# bal.net
KiCad netlist of a schematic drawn in EAGLE
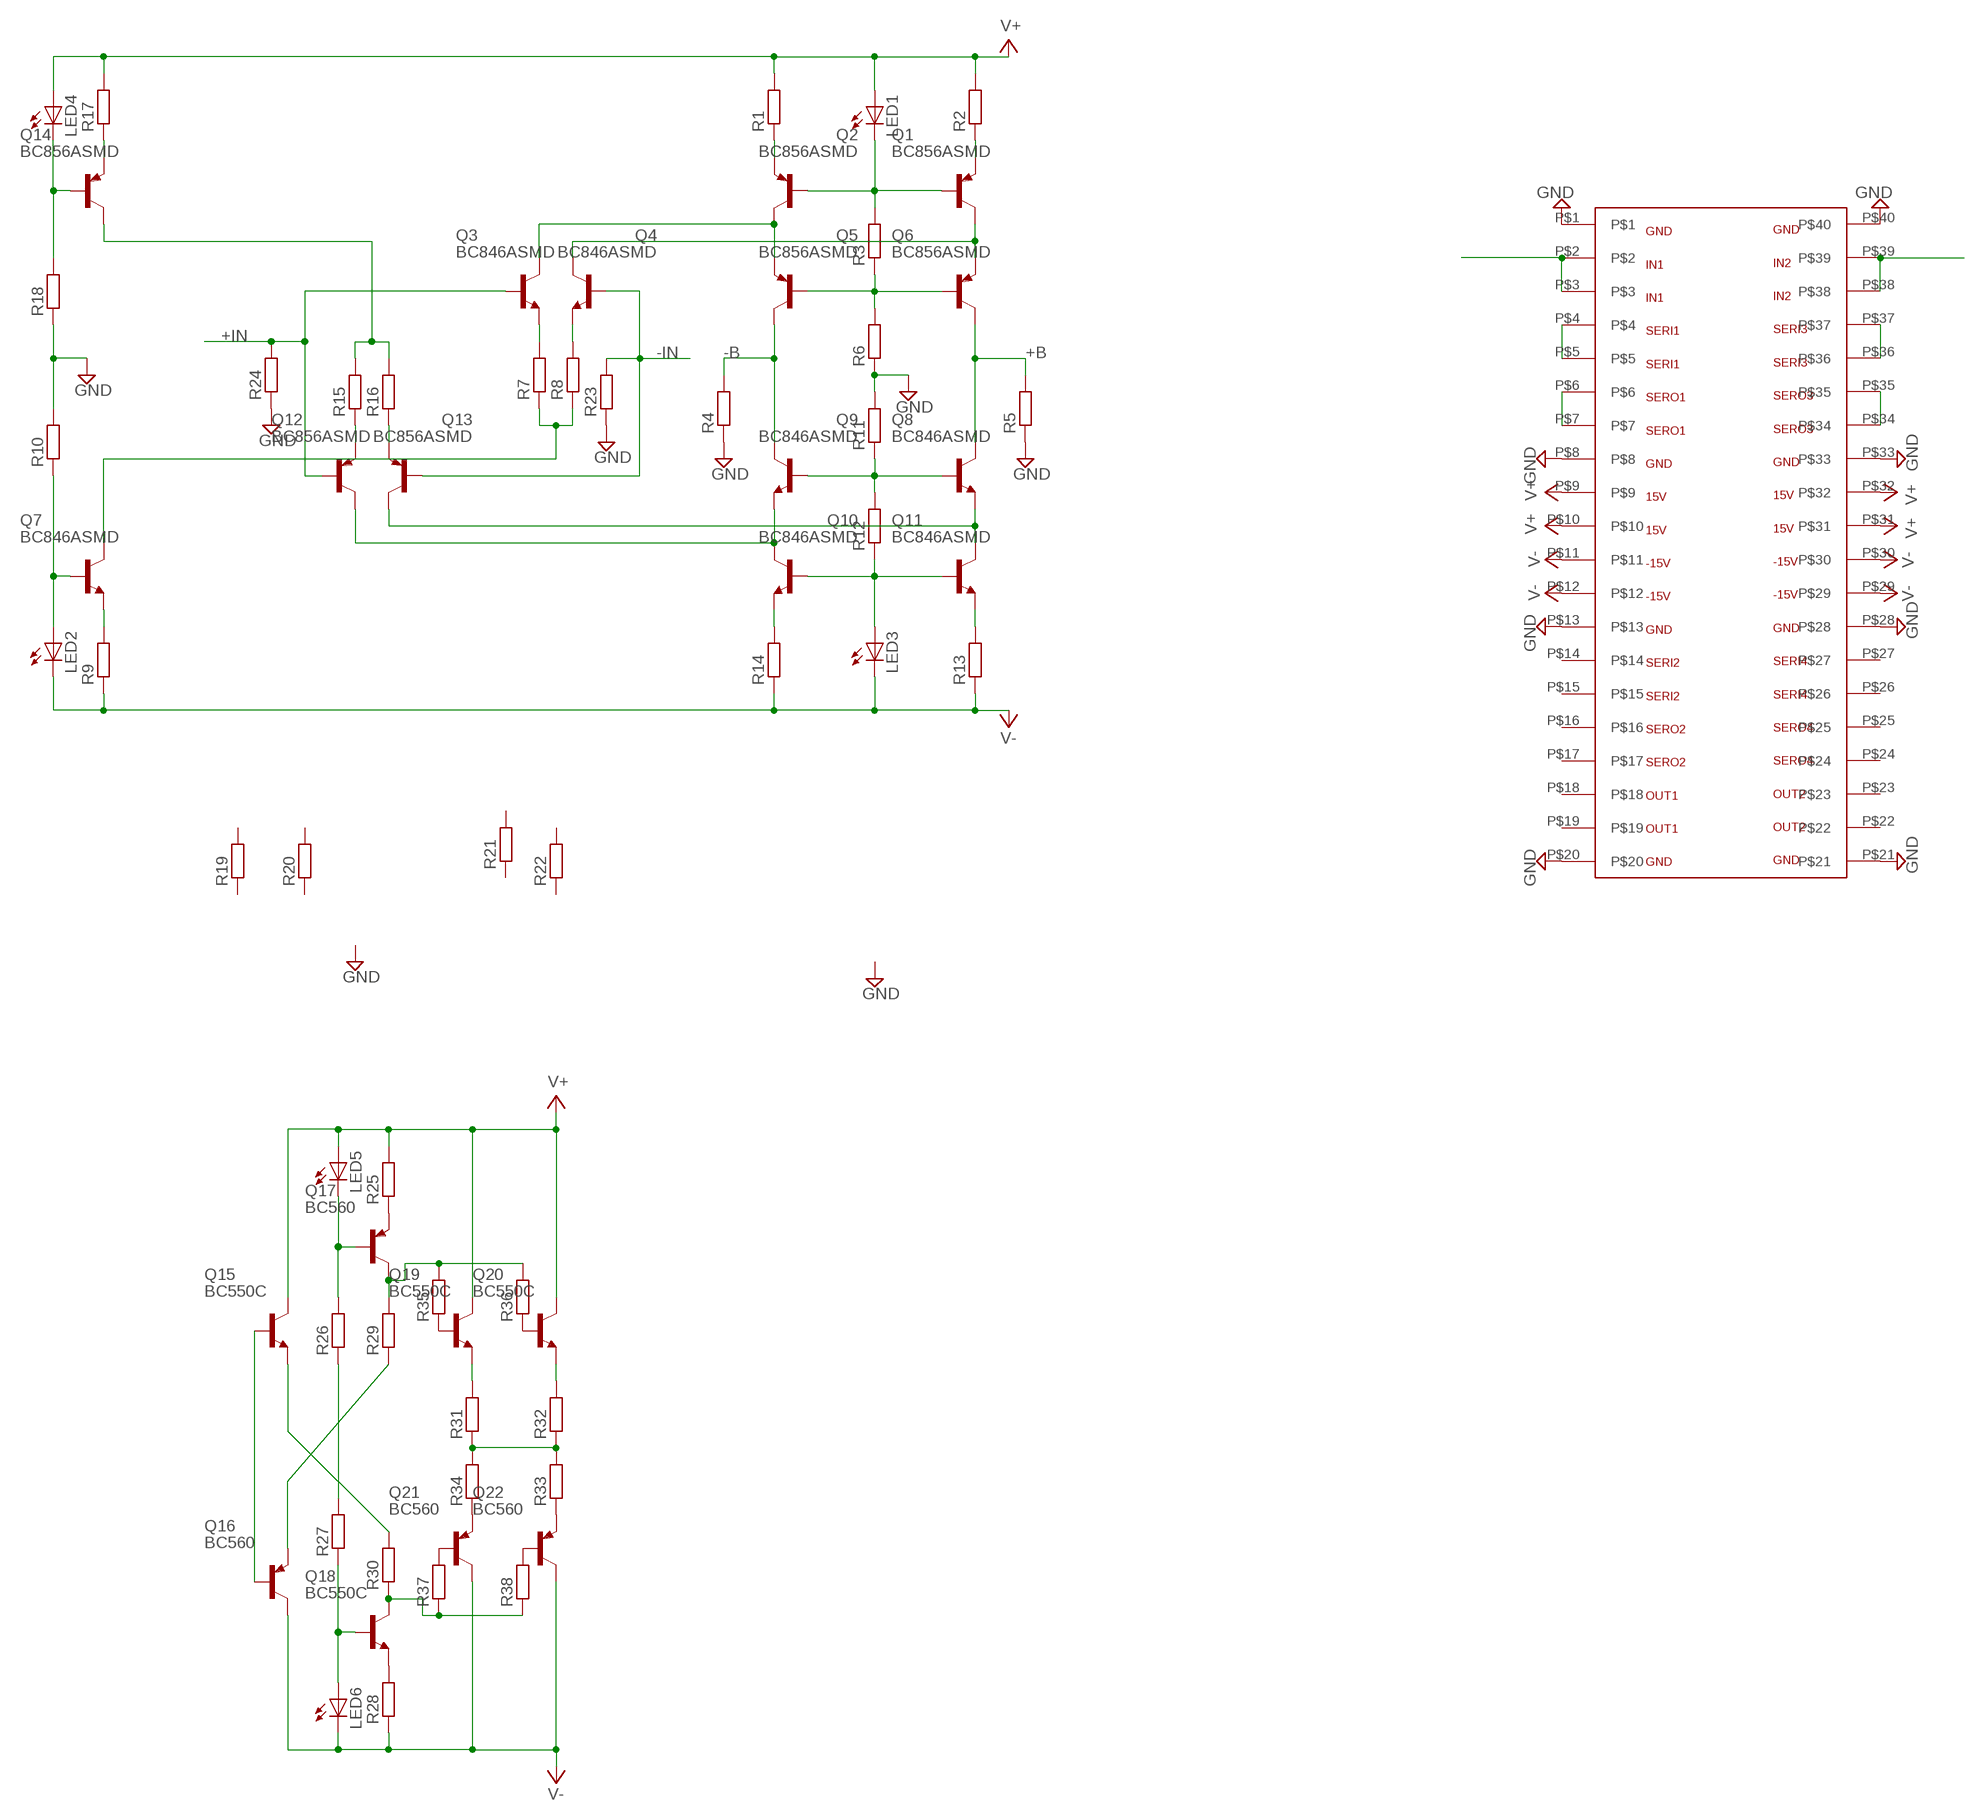
[diagram p0: schematic, sheet 1]

(export (version "E")
  (design (tool "Eeschema 10.0.6"))
  (components
    (comp (ref "LED1")
      (value "LED5MM")
      (footprint "eagle-import:LED5MM")
      (libsource (lib "eagle-import") (part "LED5MM"))
    )
    (comp (ref "LED2")
      (value "LED5MM")
      (footprint "eagle-import:LED5MM")
      (libsource (lib "eagle-import") (part "LED5MM"))
    )
    (comp (ref "LED3")
      (value "LED5MM")
      (footprint "eagle-import:LED5MM")
      (libsource (lib "eagle-import") (part "LED5MM"))
    )
    (comp (ref "LED4")
      (value "LED5MM")
      (footprint "eagle-import:LED5MM")
      (libsource (lib "eagle-import") (part "LED5MM"))
    )
    (comp (ref "LED5")
      (value "LED5MM")
      (footprint "eagle-import:LED5MM")
      (libsource (lib "eagle-import") (part "LED5MM"))
    )
    (comp (ref "LED6")
      (value "LED5MM")
      (footprint "eagle-import:LED5MM")
      (libsource (lib "eagle-import") (part "LED5MM"))
    )
    (comp (ref "Q1")
      (value "BC856ASMD")
      (footprint "eagle-import:SOT23-BEC")
      (libsource (lib "eagle-import") (part "BC856SMDA"))
    )
    (comp (ref "Q2")
      (value "BC856ASMD")
      (footprint "eagle-import:SOT23-BEC")
      (libsource (lib "eagle-import") (part "BC856SMDA"))
    )
    (comp (ref "Q3")
      (value "BC846ASMD")
      (footprint "eagle-import:SOT23")
      (libsource (lib "eagle-import") (part "BC846SMDA"))
    )
    (comp (ref "Q4")
      (value "BC846ASMD")
      (footprint "eagle-import:SOT23")
      (libsource (lib "eagle-import") (part "BC846SMDA"))
    )
    (comp (ref "Q5")
      (value "BC856ASMD")
      (footprint "eagle-import:SOT23-BEC")
      (libsource (lib "eagle-import") (part "BC856SMDA"))
    )
    (comp (ref "Q6")
      (value "BC856ASMD")
      (footprint "eagle-import:SOT23-BEC")
      (libsource (lib "eagle-import") (part "BC856SMDA"))
    )
    (comp (ref "Q7")
      (value "BC846ASMD")
      (footprint "eagle-import:SOT23")
      (libsource (lib "eagle-import") (part "BC846SMDA"))
    )
    (comp (ref "Q8")
      (value "BC846ASMD")
      (footprint "eagle-import:SOT23")
      (libsource (lib "eagle-import") (part "BC846SMDA"))
    )
    (comp (ref "Q9")
      (value "BC846ASMD")
      (footprint "eagle-import:SOT23")
      (libsource (lib "eagle-import") (part "BC846SMDA"))
    )
    (comp (ref "Q10")
      (value "BC846ASMD")
      (footprint "eagle-import:SOT23")
      (libsource (lib "eagle-import") (part "BC846SMDA"))
    )
    (comp (ref "Q11")
      (value "BC846ASMD")
      (footprint "eagle-import:SOT23")
      (libsource (lib "eagle-import") (part "BC846SMDA"))
    )
    (comp (ref "Q12")
      (value "BC856ASMD")
      (footprint "eagle-import:SOT23-BEC")
      (libsource (lib "eagle-import") (part "BC856SMDA"))
    )
    (comp (ref "Q13")
      (value "BC856ASMD")
      (footprint "eagle-import:SOT23-BEC")
      (libsource (lib "eagle-import") (part "BC856SMDA"))
    )
    (comp (ref "Q14")
      (value "BC856ASMD")
      (footprint "eagle-import:SOT23-BEC")
      (libsource (lib "eagle-import") (part "BC856SMDA"))
    )
    (comp (ref "Q15")
      (value "BC550C")
      (footprint "eagle-import:TO92-EBC")
      (libsource (lib "eagle-import") (part "BC550C"))
    )
    (comp (ref "Q16")
      (value "BC560")
      (footprint "eagle-import:TO92_1")
      (libsource (lib "eagle-import") (part "BC560"))
    )
    (comp (ref "Q17")
      (value "BC560")
      (footprint "eagle-import:TO92_1")
      (libsource (lib "eagle-import") (part "BC560"))
    )
    (comp (ref "Q18")
      (value "BC550C")
      (footprint "eagle-import:TO92-EBC")
      (libsource (lib "eagle-import") (part "BC550C"))
    )
    (comp (ref "Q19")
      (value "BC550C")
      (footprint "eagle-import:TO92-EBC")
      (libsource (lib "eagle-import") (part "BC550C"))
    )
    (comp (ref "Q20")
      (value "BC550C")
      (footprint "eagle-import:TO92-EBC")
      (libsource (lib "eagle-import") (part "BC550C"))
    )
    (comp (ref "Q21")
      (value "BC560")
      (footprint "eagle-import:TO92_1")
      (libsource (lib "eagle-import") (part "BC560"))
    )
    (comp (ref "Q22")
      (value "BC560")
      (footprint "eagle-import:TO92_1")
      (libsource (lib "eagle-import") (part "BC560"))
    )
    (comp (ref "R1")
      (value "R-EU_MELF0204W")
      (footprint "eagle-import:MINI_MELF-0204W")
      (libsource (lib "eagle-import") (part "R-EU_MELF0204W"))
    )
    (comp (ref "R2")
      (value "R-EU_MELF0204W")
      (footprint "eagle-import:MINI_MELF-0204W")
      (libsource (lib "eagle-import") (part "R-EU_MELF0204W"))
    )
    (comp (ref "R3")
      (value "R-EU_MELF0204W")
      (footprint "eagle-import:MINI_MELF-0204W")
      (libsource (lib "eagle-import") (part "R-EU_MELF0204W"))
    )
    (comp (ref "R4")
      (value "R-EU_MELF0204W")
      (footprint "eagle-import:MINI_MELF-0204W")
      (libsource (lib "eagle-import") (part "R-EU_MELF0204W"))
    )
    (comp (ref "R5")
      (value "R-EU_MELF0204W")
      (footprint "eagle-import:MINI_MELF-0204W")
      (libsource (lib "eagle-import") (part "R-EU_MELF0204W"))
    )
    (comp (ref "R6")
      (value "R-EU_MELF0204W")
      (footprint "eagle-import:MINI_MELF-0204W")
      (libsource (lib "eagle-import") (part "R-EU_MELF0204W"))
    )
    (comp (ref "R7")
      (value "R-EU_MELF0204W")
      (footprint "eagle-import:MINI_MELF-0204W")
      (libsource (lib "eagle-import") (part "R-EU_MELF0204W"))
    )
    (comp (ref "R8")
      (value "R-EU_MELF0204W")
      (footprint "eagle-import:MINI_MELF-0204W")
      (libsource (lib "eagle-import") (part "R-EU_MELF0204W"))
    )
    (comp (ref "R9")
      (value "R-EU_MELF0204W")
      (footprint "eagle-import:MINI_MELF-0204W")
      (libsource (lib "eagle-import") (part "R-EU_MELF0204W"))
    )
    (comp (ref "R10")
      (value "R-EU_MELF0204W")
      (footprint "eagle-import:MINI_MELF-0204W")
      (libsource (lib "eagle-import") (part "R-EU_MELF0204W"))
    )
    (comp (ref "R11")
      (value "R-EU_MELF0204W")
      (footprint "eagle-import:MINI_MELF-0204W")
      (libsource (lib "eagle-import") (part "R-EU_MELF0204W"))
    )
    (comp (ref "R12")
      (value "R-EU_MELF0204W")
      (footprint "eagle-import:MINI_MELF-0204W")
      (libsource (lib "eagle-import") (part "R-EU_MELF0204W"))
    )
    (comp (ref "R13")
      (value "R-EU_MELF0204W")
      (footprint "eagle-import:MINI_MELF-0204W")
      (libsource (lib "eagle-import") (part "R-EU_MELF0204W"))
    )
    (comp (ref "R14")
      (value "R-EU_MELF0204W")
      (footprint "eagle-import:MINI_MELF-0204W")
      (libsource (lib "eagle-import") (part "R-EU_MELF0204W"))
    )
    (comp (ref "R15")
      (value "R-EU_MELF0204W")
      (footprint "eagle-import:MINI_MELF-0204W")
      (libsource (lib "eagle-import") (part "R-EU_MELF0204W"))
    )
    (comp (ref "R16")
      (value "R-EU_MELF0204W")
      (footprint "eagle-import:MINI_MELF-0204W")
      (libsource (lib "eagle-import") (part "R-EU_MELF0204W"))
    )
    (comp (ref "R17")
      (value "R-EU_MELF0204W")
      (footprint "eagle-import:MINI_MELF-0204W")
      (libsource (lib "eagle-import") (part "R-EU_MELF0204W"))
    )
    (comp (ref "R18")
      (value "R-EU_MELF0204W")
      (footprint "eagle-import:MINI_MELF-0204W")
      (libsource (lib "eagle-import") (part "R-EU_MELF0204W"))
    )
    (comp (ref "R19")
      (value "R-EU_MELF0204W")
      (footprint "eagle-import:MINI_MELF-0204W")
      (libsource (lib "eagle-import") (part "R-EU_MELF0204W"))
    )
    (comp (ref "R20")
      (value "R-EU_MELF0204W")
      (footprint "eagle-import:MINI_MELF-0204W")
      (libsource (lib "eagle-import") (part "R-EU_MELF0204W"))
    )
    (comp (ref "R21")
      (value "R-EU_MELF0204W")
      (footprint "eagle-import:MINI_MELF-0204W")
      (libsource (lib "eagle-import") (part "R-EU_MELF0204W"))
    )
    (comp (ref "R22")
      (value "R-EU_MELF0204W")
      (footprint "eagle-import:MINI_MELF-0204W")
      (libsource (lib "eagle-import") (part "R-EU_MELF0204W"))
    )
    (comp (ref "R23")
      (value "R-EU_MELF0204W")
      (footprint "eagle-import:MINI_MELF-0204W")
      (libsource (lib "eagle-import") (part "R-EU_MELF0204W"))
    )
    (comp (ref "R24")
      (value "R-EU_MELF0204W")
      (footprint "eagle-import:MINI_MELF-0204W")
      (libsource (lib "eagle-import") (part "R-EU_MELF0204W"))
    )
    (comp (ref "R25")
      (value "R-EU_MELF0204W")
      (footprint "eagle-import:MINI_MELF-0204W")
      (libsource (lib "eagle-import") (part "R-EU_MELF0204W"))
    )
    (comp (ref "R26")
      (value "R-EU_MELF0204W")
      (footprint "eagle-import:MINI_MELF-0204W")
      (libsource (lib "eagle-import") (part "R-EU_MELF0204W"))
    )
    (comp (ref "R27")
      (value "R-EU_MELF0204W")
      (footprint "eagle-import:MINI_MELF-0204W")
      (libsource (lib "eagle-import") (part "R-EU_MELF0204W"))
    )
    (comp (ref "R28")
      (value "R-EU_MELF0204W")
      (footprint "eagle-import:MINI_MELF-0204W")
      (libsource (lib "eagle-import") (part "R-EU_MELF0204W"))
    )
    (comp (ref "R29")
      (value "R-EU_MELF0204W")
      (footprint "eagle-import:MINI_MELF-0204W")
      (libsource (lib "eagle-import") (part "R-EU_MELF0204W"))
    )
    (comp (ref "R30")
      (value "R-EU_MELF0204W")
      (footprint "eagle-import:MINI_MELF-0204W")
      (libsource (lib "eagle-import") (part "R-EU_MELF0204W"))
    )
    (comp (ref "R31")
      (value "R-EU_MELF0204W")
      (footprint "eagle-import:MINI_MELF-0204W")
      (libsource (lib "eagle-import") (part "R-EU_MELF0204W"))
    )
    (comp (ref "R32")
      (value "R-EU_MELF0204W")
      (footprint "eagle-import:MINI_MELF-0204W")
      (libsource (lib "eagle-import") (part "R-EU_MELF0204W"))
    )
    (comp (ref "R33")
      (value "R-EU_MELF0204W")
      (footprint "eagle-import:MINI_MELF-0204W")
      (libsource (lib "eagle-import") (part "R-EU_MELF0204W"))
    )
    (comp (ref "R34")
      (value "R-EU_MELF0204W")
      (footprint "eagle-import:MINI_MELF-0204W")
      (libsource (lib "eagle-import") (part "R-EU_MELF0204W"))
    )
    (comp (ref "R35")
      (value "R-EU_MELF0204W")
      (footprint "eagle-import:MINI_MELF-0204W")
      (libsource (lib "eagle-import") (part "R-EU_MELF0204W"))
    )
    (comp (ref "R36")
      (value "R-EU_MELF0204W")
      (footprint "eagle-import:MINI_MELF-0204W")
      (libsource (lib "eagle-import") (part "R-EU_MELF0204W"))
    )
    (comp (ref "R37")
      (value "R-EU_MELF0204W")
      (footprint "eagle-import:MINI_MELF-0204W")
      (libsource (lib "eagle-import") (part "R-EU_MELF0204W"))
    )
    (comp (ref "R38")
      (value "R-EU_MELF0204W")
      (footprint "eagle-import:MINI_MELF-0204W")
      (libsource (lib "eagle-import") (part "R-EU_MELF0204W"))
    )
    (comp (ref "U$1")
      (value "VDACA")
      (footprint "eagle-import:VDACA")
      (libsource (lib "eagle-import") (part "VDACA"))
    )
  )
  (nets
    (net (code "1") (name "/+B") (class "Default")
      (node (ref "Q6") (pin "C") (pinfunction "C_C") (pintype "passive"))
      (node (ref "Q8") (pin "3") (pinfunction "C_3") (pintype "passive"))
      (node (ref "R5") (pin "2") (pinfunction "2_2") (pintype "passive"))
    )
    (net (code "2") (name "/+IN") (class "Default")
      (node (ref "Q12") (pin "B") (pinfunction "B_B") (pintype "passive"))
      (node (ref "Q3") (pin "1") (pinfunction "B_1") (pintype "passive"))
      (node (ref "R24") (pin "2") (pinfunction "2_2") (pintype "passive"))
      (node (ref "U$1") (pin "P$2") (pinfunction "P$2_P$2") (pintype "bidirectional"))
      (node (ref "U$1") (pin "P$3") (pinfunction "P$3_P$3") (pintype "bidirectional"))
    )
    (net (code "3") (name "/-B") (class "Default")
      (node (ref "Q5") (pin "C") (pinfunction "C_C") (pintype "passive"))
      (node (ref "Q9") (pin "3") (pinfunction "C_3") (pintype "passive"))
      (node (ref "R4") (pin "2") (pinfunction "2_2") (pintype "passive"))
    )
    (net (code "4") (name "/-IN") (class "Default")
      (node (ref "Q13") (pin "B") (pinfunction "B_B") (pintype "passive"))
      (node (ref "Q4") (pin "1") (pinfunction "B_1") (pintype "passive"))
      (node (ref "R23") (pin "2") (pinfunction "2_2") (pintype "passive"))
      (node (ref "U$1") (pin "P$38") (pinfunction "P$38_P$38") (pintype "bidirectional"))
      (node (ref "U$1") (pin "P$39") (pinfunction "P$39_P$39") (pintype "bidirectional"))
    )
    (net (code "5") (name "GND") (class "Default")
      (node (ref "R10") (pin "2") (pinfunction "2_2") (pintype "passive"))
      (node (ref "R11") (pin "2") (pinfunction "2_2") (pintype "passive"))
      (node (ref "R18") (pin "1") (pinfunction "1_1") (pintype "passive"))
      (node (ref "R23") (pin "1") (pinfunction "1_1") (pintype "passive"))
      (node (ref "R24") (pin "1") (pinfunction "1_1") (pintype "passive"))
      (node (ref "R4") (pin "1") (pinfunction "1_1") (pintype "passive"))
      (node (ref "R5") (pin "1") (pinfunction "1_1") (pintype "passive"))
      (node (ref "R6") (pin "1") (pinfunction "1_1") (pintype "passive"))
      (node (ref "U$1") (pin "P$1") (pinfunction "P$1_P$1") (pintype "bidirectional"))
      (node (ref "U$1") (pin "P$13") (pinfunction "P$13_P$13") (pintype "bidirectional"))
      (node (ref "U$1") (pin "P$20") (pinfunction "P$20_P$20") (pintype "bidirectional"))
      (node (ref "U$1") (pin "P$21") (pinfunction "P$21_P$21") (pintype "bidirectional"))
      (node (ref "U$1") (pin "P$28") (pinfunction "P$28_P$28") (pintype "bidirectional"))
      (node (ref "U$1") (pin "P$33") (pinfunction "P$33_P$33") (pintype "bidirectional"))
      (node (ref "U$1") (pin "P$40") (pinfunction "P$40_P$40") (pintype "bidirectional"))
      (node (ref "U$1") (pin "P$8") (pinfunction "P$8_P$8") (pintype "bidirectional"))
    )
    (net (code "6") (name "Net-(LED1-C)") (class "Default")
      (node (ref "LED1") (pin "K") (pinfunction "C_K") (pintype "passive"))
      (node (ref "Q1") (pin "B") (pinfunction "B_B") (pintype "passive"))
      (node (ref "Q2") (pin "B") (pinfunction "B_B") (pintype "passive"))
      (node (ref "R3") (pin "2") (pinfunction "2_2") (pintype "passive"))
    )
    (net (code "7") (name "Net-(LED4-C)") (class "Default")
      (node (ref "LED4") (pin "K") (pinfunction "C_K") (pintype "passive"))
      (node (ref "Q14") (pin "B") (pinfunction "B_B") (pintype "passive"))
      (node (ref "R18") (pin "2") (pinfunction "2_2") (pintype "passive"))
    )
    (net (code "8") (name "Net-(LED5-C)") (class "Default")
      (node (ref "LED5") (pin "K") (pinfunction "C_K") (pintype "passive"))
      (node (ref "Q17") (pin "2") (pinfunction "B_2") (pintype "passive"))
      (node (ref "R26") (pin "2") (pinfunction "2_2") (pintype "passive"))
    )
    (net (code "9") (name "Net-(LED6-PadA)") (class "Default")
      (node (ref "LED6") (pin "A") (pinfunction "A_A") (pintype "passive"))
      (node (ref "Q18") (pin "B") (pinfunction "B_B") (pintype "passive"))
      (node (ref "R27") (pin "1") (pinfunction "1_1") (pintype "passive"))
    )
    (net (code "10") (name "Net-(Q1-PadE)") (class "Default")
      (node (ref "Q1") (pin "E") (pinfunction "E_E") (pintype "passive"))
      (node (ref "R2") (pin "1") (pinfunction "1_1") (pintype "passive"))
    )
    (net (code "11") (name "Net-(Q2-PadE)") (class "Default")
      (node (ref "Q2") (pin "E") (pinfunction "E_E") (pintype "passive"))
      (node (ref "R1") (pin "1") (pinfunction "1_1") (pintype "passive"))
    )
    (net (code "12") (name "Net-(Q3-C)") (class "Default")
      (node (ref "Q2") (pin "C") (pinfunction "C_C") (pintype "passive"))
      (node (ref "Q3") (pin "3") (pinfunction "C_3") (pintype "passive"))
      (node (ref "Q5") (pin "E") (pinfunction "E_E") (pintype "passive"))
    )
    (net (code "13") (name "Net-(Q3-E)") (class "Default")
      (node (ref "Q3") (pin "2") (pinfunction "E_2") (pintype "passive"))
      (node (ref "R7") (pin "2") (pinfunction "2_2") (pintype "passive"))
    )
    (net (code "14") (name "Net-(Q4-C)") (class "Default")
      (node (ref "Q1") (pin "C") (pinfunction "C_C") (pintype "passive"))
      (node (ref "Q4") (pin "3") (pinfunction "C_3") (pintype "passive"))
      (node (ref "Q6") (pin "E") (pinfunction "E_E") (pintype "passive"))
    )
    (net (code "15") (name "Net-(Q4-E)") (class "Default")
      (node (ref "Q4") (pin "2") (pinfunction "E_2") (pintype "passive"))
      (node (ref "R8") (pin "2") (pinfunction "2_2") (pintype "passive"))
    )
    (net (code "16") (name "Net-(Q5-PadB)") (class "Default")
      (node (ref "Q5") (pin "B") (pinfunction "B_B") (pintype "passive"))
      (node (ref "Q6") (pin "B") (pinfunction "B_B") (pintype "passive"))
      (node (ref "R3") (pin "1") (pinfunction "1_1") (pintype "passive"))
      (node (ref "R6") (pin "2") (pinfunction "2_2") (pintype "passive"))
    )
    (net (code "17") (name "Net-(Q7-B)") (class "Default")
      (node (ref "LED2") (pin "A") (pinfunction "A_A") (pintype "passive"))
      (node (ref "Q7") (pin "1") (pinfunction "B_1") (pintype "passive"))
      (node (ref "R10") (pin "1") (pinfunction "1_1") (pintype "passive"))
    )
    (net (code "18") (name "Net-(Q7-C)") (class "Default")
      (node (ref "Q7") (pin "3") (pinfunction "C_3") (pintype "passive"))
      (node (ref "R7") (pin "1") (pinfunction "1_1") (pintype "passive"))
      (node (ref "R8") (pin "1") (pinfunction "1_1") (pintype "passive"))
    )
    (net (code "19") (name "Net-(Q7-E)") (class "Default")
      (node (ref "Q7") (pin "2") (pinfunction "E_2") (pintype "passive"))
      (node (ref "R9") (pin "2") (pinfunction "2_2") (pintype "passive"))
    )
    (net (code "20") (name "Net-(Q8-B)") (class "Default")
      (node (ref "Q8") (pin "1") (pinfunction "B_1") (pintype "passive"))
      (node (ref "Q9") (pin "1") (pinfunction "B_1") (pintype "passive"))
      (node (ref "R11") (pin "1") (pinfunction "1_1") (pintype "passive"))
      (node (ref "R12") (pin "2") (pinfunction "2_2") (pintype "passive"))
    )
    (net (code "21") (name "Net-(Q10-B)") (class "Default")
      (node (ref "LED3") (pin "A") (pinfunction "A_A") (pintype "passive"))
      (node (ref "Q10") (pin "1") (pinfunction "B_1") (pintype "passive"))
      (node (ref "Q11") (pin "1") (pinfunction "B_1") (pintype "passive"))
      (node (ref "R12") (pin "1") (pinfunction "1_1") (pintype "passive"))
    )
    (net (code "22") (name "Net-(Q10-C)") (class "Default")
      (node (ref "Q10") (pin "3") (pinfunction "C_3") (pintype "passive"))
      (node (ref "Q12") (pin "C") (pinfunction "C_C") (pintype "passive"))
      (node (ref "Q9") (pin "2") (pinfunction "E_2") (pintype "passive"))
    )
    (net (code "23") (name "Net-(Q10-E)") (class "Default")
      (node (ref "Q10") (pin "2") (pinfunction "E_2") (pintype "passive"))
      (node (ref "R14") (pin "2") (pinfunction "2_2") (pintype "passive"))
    )
    (net (code "24") (name "Net-(Q11-C)") (class "Default")
      (node (ref "Q11") (pin "3") (pinfunction "C_3") (pintype "passive"))
      (node (ref "Q13") (pin "C") (pinfunction "C_C") (pintype "passive"))
      (node (ref "Q8") (pin "2") (pinfunction "E_2") (pintype "passive"))
    )
    (net (code "25") (name "Net-(Q11-E)") (class "Default")
      (node (ref "Q11") (pin "2") (pinfunction "E_2") (pintype "passive"))
      (node (ref "R13") (pin "2") (pinfunction "2_2") (pintype "passive"))
    )
    (net (code "26") (name "Net-(Q12-PadE)") (class "Default")
      (node (ref "Q12") (pin "E") (pinfunction "E_E") (pintype "passive"))
      (node (ref "R15") (pin "1") (pinfunction "1_1") (pintype "passive"))
    )
    (net (code "27") (name "Net-(Q13-PadE)") (class "Default")
      (node (ref "Q13") (pin "E") (pinfunction "E_E") (pintype "passive"))
      (node (ref "R16") (pin "1") (pinfunction "1_1") (pintype "passive"))
    )
    (net (code "28") (name "Net-(Q14-PadC)") (class "Default")
      (node (ref "Q14") (pin "C") (pinfunction "C_C") (pintype "passive"))
      (node (ref "R15") (pin "2") (pinfunction "2_2") (pintype "passive"))
      (node (ref "R16") (pin "2") (pinfunction "2_2") (pintype "passive"))
    )
    (net (code "29") (name "Net-(Q14-PadE)") (class "Default")
      (node (ref "Q14") (pin "E") (pinfunction "E_E") (pintype "passive"))
      (node (ref "R17") (pin "1") (pinfunction "1_1") (pintype "passive"))
    )
    (net (code "30") (name "Net-(Q15-PadE)") (class "Default")
      (node (ref "Q15") (pin "E") (pinfunction "E_E") (pintype "passive"))
      (node (ref "R30") (pin "2") (pinfunction "2_2") (pintype "passive"))
    )
    (net (code "31") (name "Net-(Q16-B)") (class "Default")
      (node (ref "Q15") (pin "B") (pinfunction "B_B") (pintype "passive"))
      (node (ref "Q16") (pin "2") (pinfunction "B_2") (pintype "passive"))
    )
    (net (code "32") (name "Net-(Q16-E)") (class "Default")
      (node (ref "Q16") (pin "3") (pinfunction "E_3") (pintype "passive"))
      (node (ref "R29") (pin "1") (pinfunction "1_1") (pintype "passive"))
    )
    (net (code "33") (name "Net-(Q17-C)") (class "Default")
      (node (ref "Q17") (pin "1") (pinfunction "C_1") (pintype "passive"))
      (node (ref "R29") (pin "2") (pinfunction "2_2") (pintype "passive"))
      (node (ref "R35") (pin "2") (pinfunction "2_2") (pintype "passive"))
      (node (ref "R36") (pin "2") (pinfunction "2_2") (pintype "passive"))
    )
    (net (code "34") (name "Net-(Q17-E)") (class "Default")
      (node (ref "Q17") (pin "3") (pinfunction "E_3") (pintype "passive"))
      (node (ref "R25") (pin "1") (pinfunction "1_1") (pintype "passive"))
    )
    (net (code "35") (name "Net-(Q18-PadC)") (class "Default")
      (node (ref "Q18") (pin "C") (pinfunction "C_C") (pintype "passive"))
      (node (ref "R30") (pin "1") (pinfunction "1_1") (pintype "passive"))
      (node (ref "R37") (pin "1") (pinfunction "1_1") (pintype "passive"))
      (node (ref "R38") (pin "1") (pinfunction "1_1") (pintype "passive"))
    )
    (net (code "36") (name "Net-(Q18-PadE)") (class "Default")
      (node (ref "Q18") (pin "E") (pinfunction "E_E") (pintype "passive"))
      (node (ref "R28") (pin "2") (pinfunction "2_2") (pintype "passive"))
    )
    (net (code "37") (name "Net-(Q19-PadB)") (class "Default")
      (node (ref "Q19") (pin "B") (pinfunction "B_B") (pintype "passive"))
      (node (ref "R35") (pin "1") (pinfunction "1_1") (pintype "passive"))
    )
    (net (code "38") (name "Net-(Q19-PadE)") (class "Default")
      (node (ref "Q19") (pin "E") (pinfunction "E_E") (pintype "passive"))
      (node (ref "R31") (pin "2") (pinfunction "2_2") (pintype "passive"))
    )
    (net (code "39") (name "Net-(Q20-PadB)") (class "Default")
      (node (ref "Q20") (pin "B") (pinfunction "B_B") (pintype "passive"))
      (node (ref "R36") (pin "1") (pinfunction "1_1") (pintype "passive"))
    )
    (net (code "40") (name "Net-(Q20-PadE)") (class "Default")
      (node (ref "Q20") (pin "E") (pinfunction "E_E") (pintype "passive"))
      (node (ref "R32") (pin "2") (pinfunction "2_2") (pintype "passive"))
    )
    (net (code "41") (name "Net-(Q21-B)") (class "Default")
      (node (ref "Q21") (pin "2") (pinfunction "B_2") (pintype "passive"))
      (node (ref "R37") (pin "2") (pinfunction "2_2") (pintype "passive"))
    )
    (net (code "42") (name "Net-(Q21-E)") (class "Default")
      (node (ref "Q21") (pin "3") (pinfunction "E_3") (pintype "passive"))
      (node (ref "R34") (pin "1") (pinfunction "1_1") (pintype "passive"))
    )
    (net (code "43") (name "Net-(Q22-B)") (class "Default")
      (node (ref "Q22") (pin "2") (pinfunction "B_2") (pintype "passive"))
      (node (ref "R38") (pin "2") (pinfunction "2_2") (pintype "passive"))
    )
    (net (code "44") (name "Net-(Q22-E)") (class "Default")
      (node (ref "Q22") (pin "3") (pinfunction "E_3") (pintype "passive"))
      (node (ref "R33") (pin "1") (pinfunction "1_1") (pintype "passive"))
    )
    (net (code "45") (name "Net-(R26-Pad1)") (class "Default")
      (node (ref "R26") (pin "1") (pinfunction "1_1") (pintype "passive"))
      (node (ref "R27") (pin "2") (pinfunction "2_2") (pintype "passive"))
    )
    (net (code "46") (name "Net-(R31-Pad1)") (class "Default")
      (node (ref "R31") (pin "1") (pinfunction "1_1") (pintype "passive"))
      (node (ref "R32") (pin "1") (pinfunction "1_1") (pintype "passive"))
      (node (ref "R33") (pin "2") (pinfunction "2_2") (pintype "passive"))
      (node (ref "R34") (pin "2") (pinfunction "2_2") (pintype "passive"))
    )
    (net (code "47") (name "Net-(U$1-PadP$4)") (class "Default")
      (node (ref "U$1") (pin "P$4") (pinfunction "P$4_P$4") (pintype "bidirectional"))
      (node (ref "U$1") (pin "P$5") (pinfunction "P$5_P$5") (pintype "bidirectional"))
    )
    (net (code "48") (name "Net-(U$1-PadP$6)") (class "Default")
      (node (ref "U$1") (pin "P$6") (pinfunction "P$6_P$6") (pintype "bidirectional"))
      (node (ref "U$1") (pin "P$7") (pinfunction "P$7_P$7") (pintype "bidirectional"))
    )
    (net (code "49") (name "Net-(U$1-PadP$34)") (class "Default")
      (node (ref "U$1") (pin "P$34") (pinfunction "P$34_P$34") (pintype "bidirectional"))
      (node (ref "U$1") (pin "P$35") (pinfunction "P$35_P$35") (pintype "bidirectional"))
    )
    (net (code "50") (name "Net-(U$1-PadP$36)") (class "Default")
      (node (ref "U$1") (pin "P$36") (pinfunction "P$36_P$36") (pintype "bidirectional"))
      (node (ref "U$1") (pin "P$37") (pinfunction "P$37_P$37") (pintype "bidirectional"))
    )
    (net (code "51") (name "V+") (class "Default")
      (node (ref "LED1") (pin "A") (pinfunction "A_A") (pintype "passive"))
      (node (ref "LED4") (pin "A") (pinfunction "A_A") (pintype "passive"))
      (node (ref "LED5") (pin "A") (pinfunction "A_A") (pintype "passive"))
      (node (ref "Q15") (pin "C") (pinfunction "C_C") (pintype "passive"))
      (node (ref "Q19") (pin "C") (pinfunction "C_C") (pintype "passive"))
      (node (ref "Q20") (pin "C") (pinfunction "C_C") (pintype "passive"))
      (node (ref "R1") (pin "2") (pinfunction "2_2") (pintype "passive"))
      (node (ref "R17") (pin "2") (pinfunction "2_2") (pintype "passive"))
      (node (ref "R2") (pin "2") (pinfunction "2_2") (pintype "passive"))
      (node (ref "R25") (pin "2") (pinfunction "2_2") (pintype "passive"))
      (node (ref "U$1") (pin "P$10") (pinfunction "P$10_P$10") (pintype "bidirectional"))
      (node (ref "U$1") (pin "P$31") (pinfunction "P$31_P$31") (pintype "bidirectional"))
      (node (ref "U$1") (pin "P$32") (pinfunction "P$32_P$32") (pintype "bidirectional"))
      (node (ref "U$1") (pin "P$9") (pinfunction "P$9_P$9") (pintype "bidirectional"))
    )
    (net (code "52") (name "V-") (class "Default")
      (node (ref "LED2") (pin "K") (pinfunction "C_K") (pintype "passive"))
      (node (ref "LED3") (pin "K") (pinfunction "C_K") (pintype "passive"))
      (node (ref "LED6") (pin "K") (pinfunction "C_K") (pintype "passive"))
      (node (ref "Q16") (pin "1") (pinfunction "C_1") (pintype "passive"))
      (node (ref "Q21") (pin "1") (pinfunction "C_1") (pintype "passive"))
      (node (ref "Q22") (pin "1") (pinfunction "C_1") (pintype "passive"))
      (node (ref "R13") (pin "1") (pinfunction "1_1") (pintype "passive"))
      (node (ref "R14") (pin "1") (pinfunction "1_1") (pintype "passive"))
      (node (ref "R28") (pin "1") (pinfunction "1_1") (pintype "passive"))
      (node (ref "R9") (pin "1") (pinfunction "1_1") (pintype "passive"))
      (node (ref "U$1") (pin "P$11") (pinfunction "P$11_P$11") (pintype "bidirectional"))
      (node (ref "U$1") (pin "P$12") (pinfunction "P$12_P$12") (pintype "bidirectional"))
      (node (ref "U$1") (pin "P$29") (pinfunction "P$29_P$29") (pintype "bidirectional"))
      (node (ref "U$1") (pin "P$30") (pinfunction "P$30_P$30") (pintype "bidirectional"))
    )
    (net (code "53") (name "unconnected-(R19-Pad1)") (class "Default")
      (node (ref "R19") (pin "1") (pinfunction "1_1") (pintype "passive"))
    )
    (net (code "54") (name "unconnected-(R19-Pad2)") (class "Default")
      (node (ref "R19") (pin "2") (pinfunction "2_2") (pintype "passive"))
    )
    (net (code "55") (name "unconnected-(R20-Pad1)") (class "Default")
      (node (ref "R20") (pin "1") (pinfunction "1_1") (pintype "passive"))
    )
    (net (code "56") (name "unconnected-(R20-Pad2)") (class "Default")
      (node (ref "R20") (pin "2") (pinfunction "2_2") (pintype "passive"))
    )
    (net (code "57") (name "unconnected-(R21-Pad1)") (class "Default")
      (node (ref "R21") (pin "1") (pinfunction "1_1") (pintype "passive"))
    )
    (net (code "58") (name "unconnected-(R21-Pad2)") (class "Default")
      (node (ref "R21") (pin "2") (pinfunction "2_2") (pintype "passive"))
    )
    (net (code "59") (name "unconnected-(R22-Pad1)") (class "Default")
      (node (ref "R22") (pin "1") (pinfunction "1_1") (pintype "passive"))
    )
    (net (code "60") (name "unconnected-(R22-Pad2)") (class "Default")
      (node (ref "R22") (pin "2") (pinfunction "2_2") (pintype "passive"))
    )
    (net (code "61") (name "unconnected-(U$1-PadP$14)") (class "Default")
      (node (ref "U$1") (pin "P$14") (pinfunction "P$14_P$14") (pintype "bidirectional"))
    )
    (net (code "62") (name "unconnected-(U$1-PadP$15)") (class "Default")
      (node (ref "U$1") (pin "P$15") (pinfunction "P$15_P$15") (pintype "bidirectional"))
    )
    (net (code "63") (name "unconnected-(U$1-PadP$16)") (class "Default")
      (node (ref "U$1") (pin "P$16") (pinfunction "P$16_P$16") (pintype "bidirectional"))
    )
    (net (code "64") (name "unconnected-(U$1-PadP$17)") (class "Default")
      (node (ref "U$1") (pin "P$17") (pinfunction "P$17_P$17") (pintype "bidirectional"))
    )
    (net (code "65") (name "unconnected-(U$1-PadP$18)") (class "Default")
      (node (ref "U$1") (pin "P$18") (pinfunction "P$18_P$18") (pintype "bidirectional"))
    )
    (net (code "66") (name "unconnected-(U$1-PadP$19)") (class "Default")
      (node (ref "U$1") (pin "P$19") (pinfunction "P$19_P$19") (pintype "bidirectional"))
    )
    (net (code "67") (name "unconnected-(U$1-PadP$22)") (class "Default")
      (node (ref "U$1") (pin "P$22") (pinfunction "P$22_P$22") (pintype "bidirectional"))
    )
    (net (code "68") (name "unconnected-(U$1-PadP$23)") (class "Default")
      (node (ref "U$1") (pin "P$23") (pinfunction "P$23_P$23") (pintype "bidirectional"))
    )
    (net (code "69") (name "unconnected-(U$1-PadP$24)") (class "Default")
      (node (ref "U$1") (pin "P$24") (pinfunction "P$24_P$24") (pintype "bidirectional"))
    )
    (net (code "70") (name "unconnected-(U$1-PadP$25)") (class "Default")
      (node (ref "U$1") (pin "P$25") (pinfunction "P$25_P$25") (pintype "bidirectional"))
    )
    (net (code "71") (name "unconnected-(U$1-PadP$26)") (class "Default")
      (node (ref "U$1") (pin "P$26") (pinfunction "P$26_P$26") (pintype "bidirectional"))
    )
    (net (code "72") (name "unconnected-(U$1-PadP$27)") (class "Default")
      (node (ref "U$1") (pin "P$27") (pinfunction "P$27_P$27") (pintype "bidirectional"))
    )
  )
)
